# main.net
KiCad netlist of a schematic drawn in Altium Designer
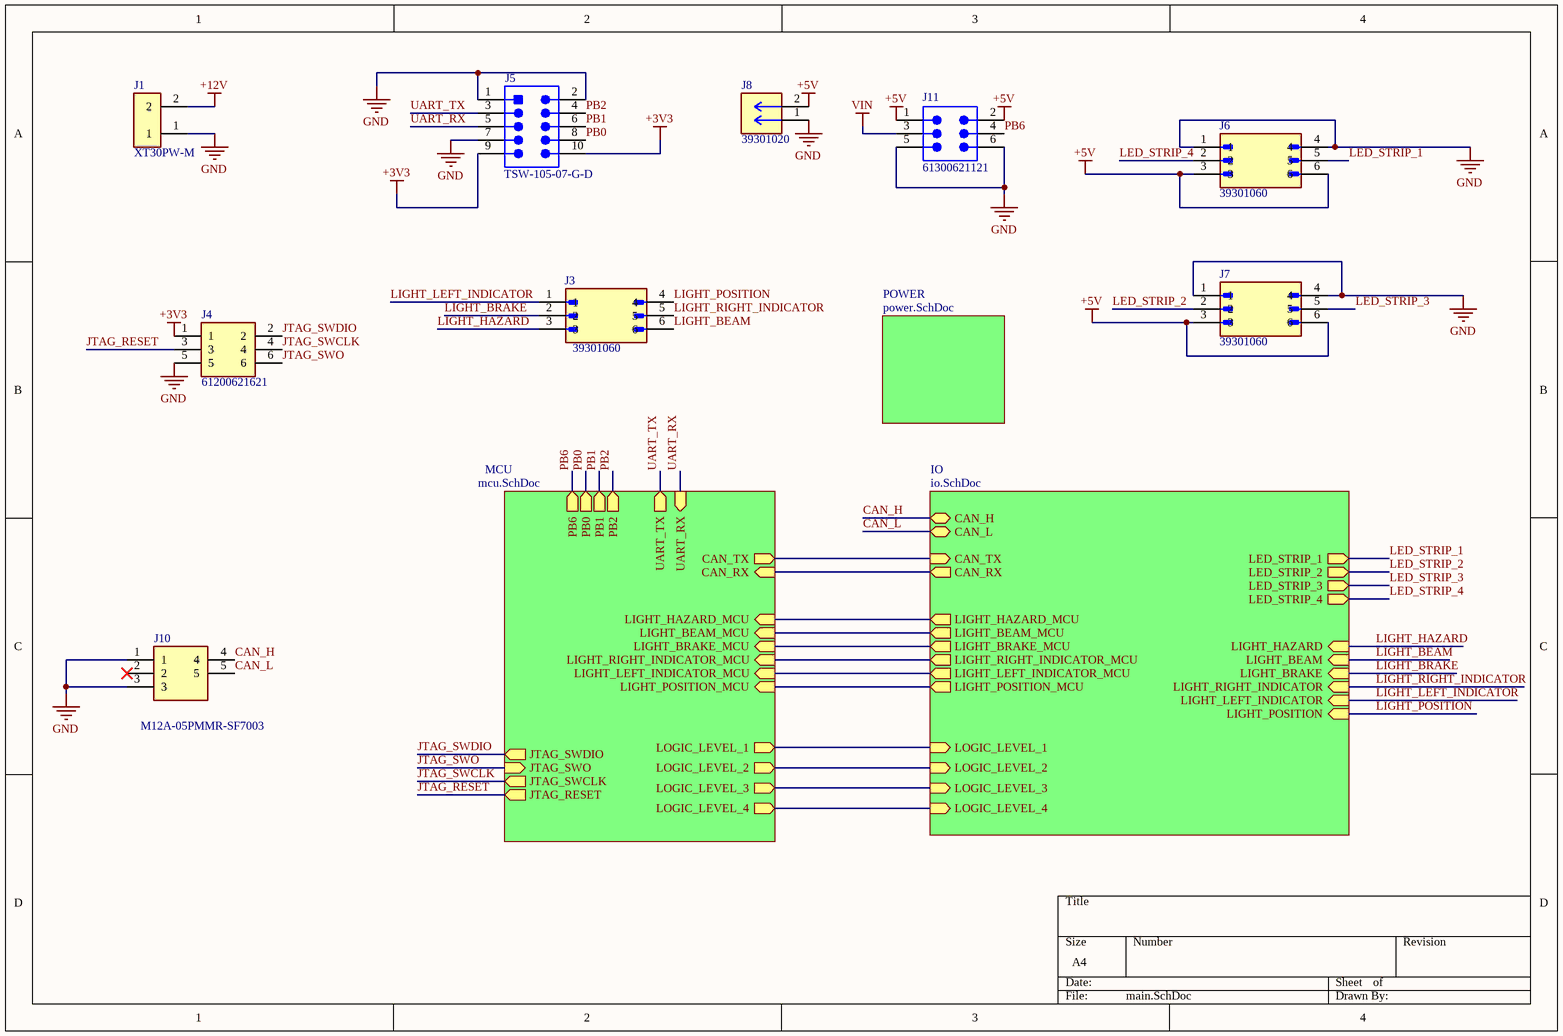
[diagram p0: main.SchDoc]

(export (version "E")
  (design (tool "Eeschema 10.0.6"))
  (components
    (comp (ref "J1")
      (value "XT30PW-M")
      (footprint "XT30PWM")
      (description "Plug; XT30; Male; 30A; Low Temperature Rise Fire Retardant")
      (libsource (lib "HydrogreenLibrary") (part "XT30PW-M"))
    )
    (comp (ref "J3")
      (value "39301060")
      (footprint "39301060")
      (description "Mini-Fit Jr. Through Hole PCB Header, Right Angle, 6 Contacts, 2 Rows, 4.2mm Pitch")
      (fields (field (name "MANUFACTURER") "Molex") (field (name "MANUFACTURER PART NUMBER") "39-30-1060"))
      (libsource (lib "HydrogreenLibrary") (part "39301060"))
    )
    (comp (ref "J4")
      (value "61200621621")
      (footprint "61200621621")
      (description "Conn Shrouded Header (4 Sides) M 6 POS 2.54mm Solder ST Top Entry Thru-Hole Tray")
      (fields
        (field (name "MOUSER PART NUMBER") "710-61200621621")
        (field (name "MANUFACTURER") "Wurth Elektronik")
      )
      (libsource (lib "HydrogreenLibrary") (part "61200621621"))
    )
    (comp (ref "J5")
      (value "TSW-105-07-G-D")
      (footprint "SMTC-TSW-105-07-G-D_V")
      (fields (field (name "MANUFACTURER") "Samtec-Inc."))
      (libsource (lib "Altium Content Vault") (part "CN-2P-M-R10"))
    )
    (comp (ref "J6")
      (value "39301060")
      (footprint "39301060")
      (description "Mini-Fit Jr. Through Hole PCB Header, Right Angle, 6 Contacts, 2 Rows, 4.2mm Pitch")
      (fields (field (name "MANUFACTURER") "Molex") (field (name "MANUFACTURER PART NUMBER") "39-30-1060"))
      (libsource (lib "HydrogreenLibrary") (part "39301060"))
    )
    (comp (ref "J7")
      (value "39301060")
      (footprint "39301060")
      (description "Mini-Fit Jr. Through Hole PCB Header, Right Angle, 6 Contacts, 2 Rows, 4.2mm Pitch")
      (fields (field (name "MANUFACTURER") "Molex") (field (name "MANUFACTURER PART NUMBER") "39-30-1060"))
      (libsource (lib "HydrogreenLibrary") (part "39301060"))
    )
    (comp (ref "J8")
      (value "39301020")
      (footprint "39301020")
      (description "Pin Header, Power, 2 Rows, 2 Contacts, Through Hole Right Angle, Mini-Fit Jr. 5569")
      (fields (field (name "MF") "Molex") (field (name "MANUFACTURER PART NUMBER") "39-30-1020"))
      (libsource (lib "HydrogreenLibrary") (part "39301020"))
    )
    (comp (ref "J10")
      (value "M12A-05PMMR-SF7003")
      (footprint "M12A05PMMRSF7003")
      (description "M12, A Code, 4A, 05 pins, Male Contact, Hexagonal, M12*1.0, PCB 90ø, Front Fastened, IP67")
      (fields
        (field (name "MOUSER PART NUMBER") "523-M12A05PMMRSF7003")
        (field (name "MANUFACTURER") "Amphenol LTW")
      )
      (libsource (lib "HydrogreenLibrary") (part "M12A-05PMMR-SF7003"))
    )
    (comp (ref "J11")
      (value "61300621121")
      (footprint "61300621121")
      (libsource (lib "Altium Content Vault") (part "Header_Male_2R_06P"))
    )
  )
  (nets
    (net (code "1") (name "+3V3") (class "Default")
      (node (ref "J4") (pin "1") (pinfunction "1_1") (pintype "passive"))
      (node (ref "J5") (pin "10") (pinfunction "10_10") (pintype "passive"))
      (node (ref "J5") (pin "9") (pinfunction "9_9") (pintype "passive"))
    )
    (net (code "2") (name "+5V") (class "Default")
      (node (ref "J11") (pin "1") (pinfunction "1_1") (pintype "passive"))
      (node (ref "J11") (pin "2") (pinfunction "2_2") (pintype "passive"))
      (node (ref "J6") (pin "3") (pinfunction "3_3") (pintype "passive"))
      (node (ref "J6") (pin "6") (pinfunction "6_6") (pintype "passive"))
      (node (ref "J7") (pin "3") (pinfunction "3_3") (pintype "passive"))
      (node (ref "J7") (pin "6") (pinfunction "6_6") (pintype "passive"))
      (node (ref "J8") (pin "2") (pinfunction "2_2") (pintype "passive"))
    )
    (net (code "3") (name "+12V") (class "Default")
      (node (ref "J1") (pin "2") (pinfunction "2_2") (pintype "passive"))
    )
    (net (code "4") (name "/CAN_H") (class "Default")
      (node (ref "J10") (pin "4") (pinfunction "4_4") (pintype "passive"))
    )
    (net (code "5") (name "/CAN_L") (class "Default")
      (node (ref "J10") (pin "5") (pinfunction "5_5") (pintype "passive"))
    )
    (net (code "8") (name "/JTAG_RESET") (class "Default")
      (node (ref "J4") (pin "3") (pinfunction "3_3") (pintype "passive"))
    )
    (net (code "9") (name "/JTAG_SWCLK") (class "Default")
      (node (ref "J4") (pin "4") (pinfunction "4_4") (pintype "passive"))
    )
    (net (code "10") (name "/JTAG_SWDIO") (class "Default")
      (node (ref "J4") (pin "2") (pinfunction "2_2") (pintype "passive"))
    )
    (net (code "11") (name "/JTAG_SWO") (class "Default")
      (node (ref "J4") (pin "6") (pinfunction "6_6") (pintype "passive"))
    )
    (net (code "12") (name "/LED_STRIP_1") (class "Default")
      (node (ref "J6") (pin "5") (pinfunction "5_5") (pintype "passive"))
    )
    (net (code "13") (name "/LED_STRIP_2") (class "Default")
      (node (ref "J7") (pin "2") (pinfunction "2_2") (pintype "passive"))
    )
    (net (code "14") (name "/LED_STRIP_3") (class "Default")
      (node (ref "J7") (pin "5") (pinfunction "5_5") (pintype "passive"))
    )
    (net (code "15") (name "/LED_STRIP_4") (class "Default")
      (node (ref "J6") (pin "2") (pinfunction "2_2") (pintype "passive"))
    )
    (net (code "16") (name "/LIGHT_BEAM") (class "Default")
      (node (ref "J3") (pin "6") (pinfunction "6_6") (pintype "passive"))
    )
    (net (code "18") (name "/LIGHT_BRAKE") (class "Default")
      (node (ref "J3") (pin "2") (pinfunction "2_2") (pintype "passive"))
    )
    (net (code "20") (name "/LIGHT_HAZARD") (class "Default")
      (node (ref "J3") (pin "3") (pinfunction "3_3") (pintype "passive"))
    )
    (net (code "22") (name "/LIGHT_LEFT_INDICATOR") (class "Default")
      (node (ref "J3") (pin "1") (pinfunction "1_1") (pintype "passive"))
    )
    (net (code "24") (name "/LIGHT_POSITION") (class "Default")
      (node (ref "J3") (pin "4") (pinfunction "4_4") (pintype "passive"))
    )
    (net (code "26") (name "/LIGHT_RIGHT_INDICATOR") (class "Default")
      (node (ref "J3") (pin "5") (pinfunction "5_5") (pintype "passive"))
    )
    (net (code "32") (name "/PB0") (class "Default")
      (node (ref "J5") (pin "8") (pinfunction "8_8") (pintype "passive"))
    )
    (net (code "33") (name "/PB1") (class "Default")
      (node (ref "J5") (pin "6") (pinfunction "6_6") (pintype "passive"))
    )
    (net (code "34") (name "/PB2") (class "Default")
      (node (ref "J5") (pin "4") (pinfunction "4_4") (pintype "passive"))
    )
    (net (code "35") (name "/PB6") (class "Default")
      (node (ref "J11") (pin "4") (pinfunction "4_4") (pintype "passive"))
    )
    (net (code "36") (name "/UART_RX") (class "Default")
      (node (ref "J5") (pin "5") (pinfunction "5_5") (pintype "passive"))
    )
    (net (code "37") (name "/UART_TX") (class "Default")
      (node (ref "J5") (pin "3") (pinfunction "3_3") (pintype "passive"))
    )
    (net (code "38") (name "GND") (class "Default")
      (node (ref "J1") (pin "1") (pinfunction "1_1") (pintype "passive"))
      (node (ref "J10") (pin "1") (pinfunction "1_1") (pintype "passive"))
      (node (ref "J10") (pin "3") (pinfunction "3_3") (pintype "passive"))
      (node (ref "J11") (pin "5") (pinfunction "5_5") (pintype "passive"))
      (node (ref "J11") (pin "6") (pinfunction "6_6") (pintype "passive"))
      (node (ref "J4") (pin "5") (pinfunction "5_5") (pintype "passive"))
      (node (ref "J5") (pin "1") (pinfunction "1_1") (pintype "passive"))
      (node (ref "J5") (pin "2") (pinfunction "2_2") (pintype "passive"))
      (node (ref "J5") (pin "7") (pinfunction "7_7") (pintype "passive"))
      (node (ref "J6") (pin "1") (pinfunction "1_1") (pintype "passive"))
      (node (ref "J6") (pin "4") (pinfunction "4_4") (pintype "passive"))
      (node (ref "J7") (pin "1") (pinfunction "1_1") (pintype "passive"))
      (node (ref "J7") (pin "4") (pinfunction "4_4") (pintype "passive"))
      (node (ref "J8") (pin "1") (pinfunction "1_1") (pintype "passive"))
    )
    (net (code "39") (name "VIN") (class "Default")
      (node (ref "J11") (pin "3") (pinfunction "3_3") (pintype "passive"))
    )
    (net (code "40") (name "unconnected-(J10-Pad2)") (class "Default")
      (node (ref "J10") (pin "2") (pinfunction "2_2") (pintype "passive+no_connect"))
    )
  )
)
